# digibuttons.net
KiCad netlist of a schematic drawn in EAGLE
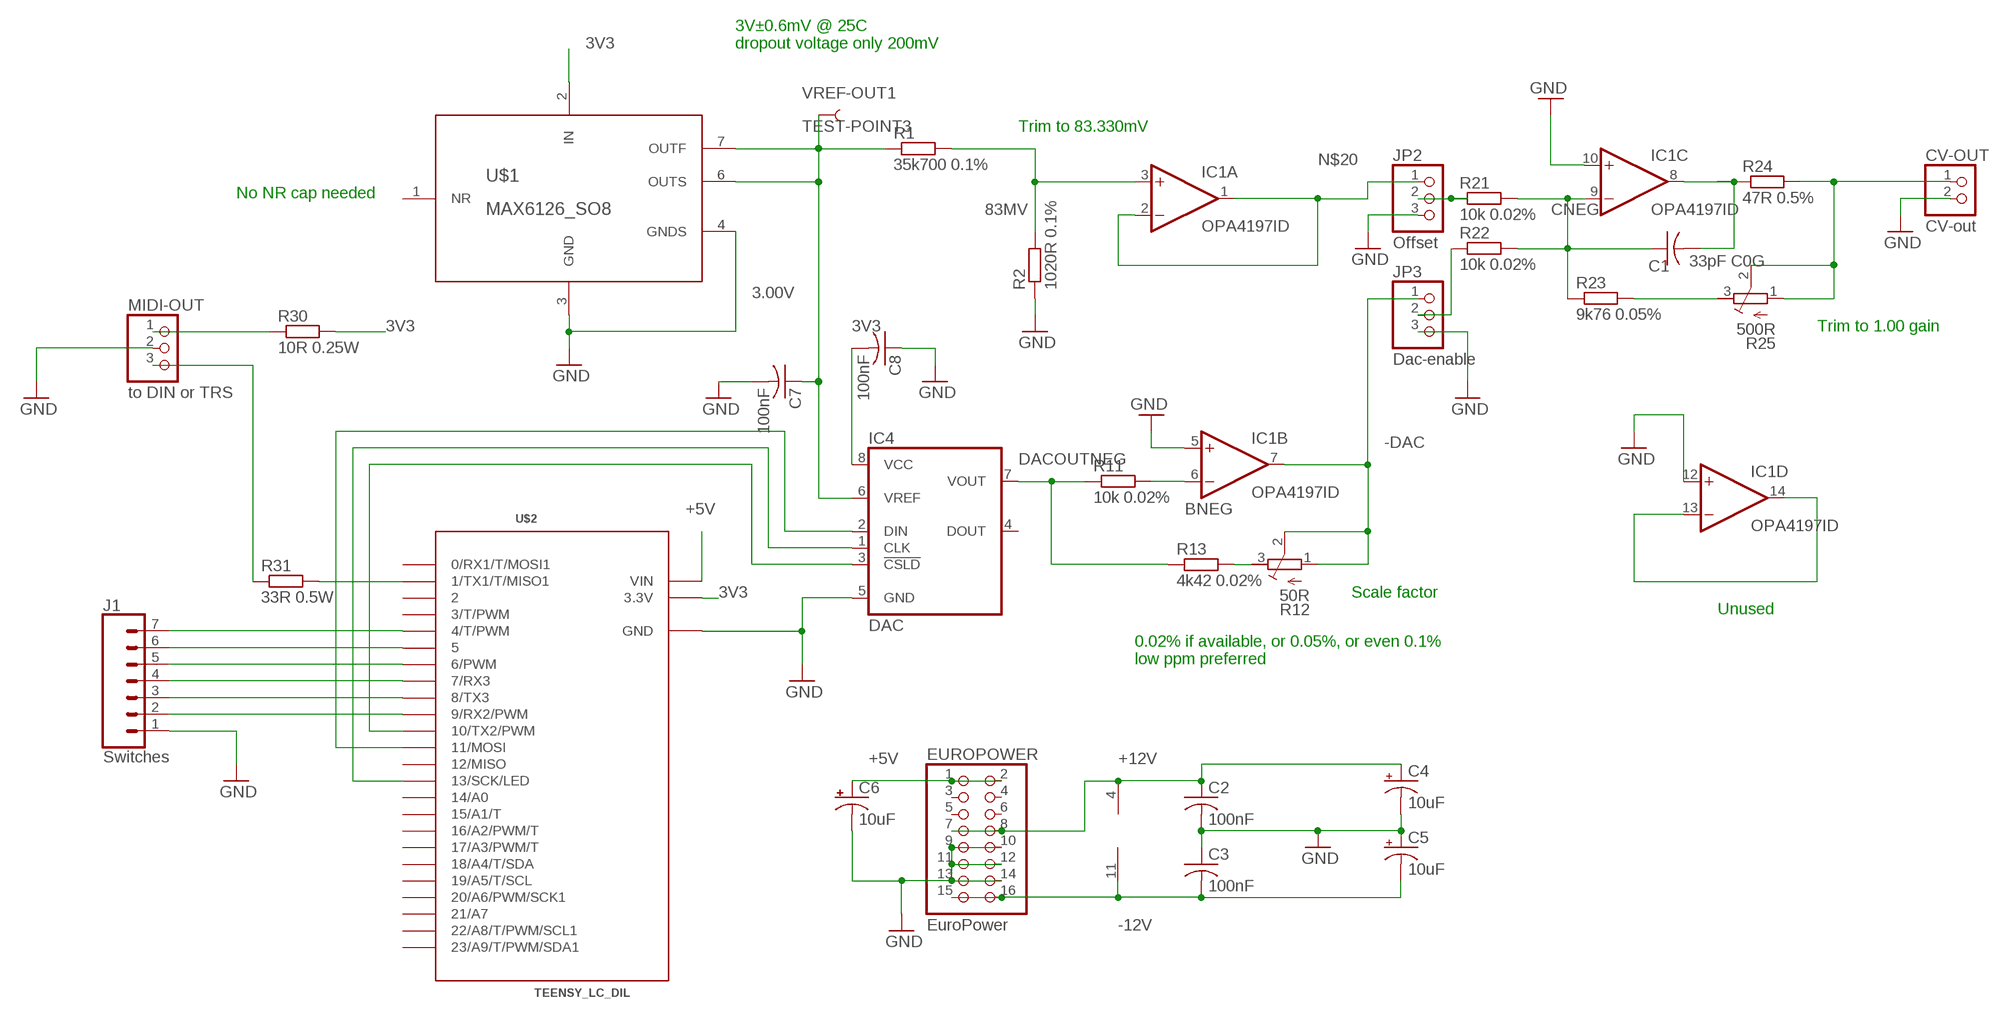
[diagram p0: schematic, sheet 1]

(export (version "E")
  (design (tool "Eeschema 10.0.6"))
  (components
    (comp (ref "C1")
      (value "33pF C0G")
      (footprint "eagle-import:C0805")
      (libsource (lib "eagle-import") (part "C-USC0805"))
    )
    (comp (ref "C2")
      (value "100nF")
      (footprint "eagle-import:C1206")
      (libsource (lib "eagle-import") (part "C-USC1206"))
    )
    (comp (ref "C3")
      (value "100nF")
      (footprint "eagle-import:C1206")
      (libsource (lib "eagle-import") (part "C-USC1206"))
    )
    (comp (ref "C4")
      (value "10uF")
      (footprint "eagle-import:CPOL-RADIAL-2.5MM-5MM")
      (libsource (lib "eagle-import") (part "10UF-POLAR-RADIAL-2.5MM-25V-20%"))
    )
    (comp (ref "C5")
      (value "10uF")
      (footprint "eagle-import:CPOL-RADIAL-2.5MM-5MM")
      (libsource (lib "eagle-import") (part "10UF-POLAR-RADIAL-2.5MM-25V-20%"))
    )
    (comp (ref "C6")
      (value "10uF")
      (footprint "eagle-import:CPOL-RADIAL-2.5MM-5MM")
      (libsource (lib "eagle-import") (part "10UF-POLAR-RADIAL-2.5MM-25V-20%"))
    )
    (comp (ref "C7")
      (value "100nF")
      (footprint "eagle-import:C1206")
      (libsource (lib "eagle-import") (part "C-USC1206"))
    )
    (comp (ref "C8")
      (value "100nF")
      (footprint "eagle-import:C1206")
      (libsource (lib "eagle-import") (part "C-USC1206"))
    )
    (comp (ref "CV-OUT")
      (value "CV-out")
      (footprint "eagle-import:1X02")
      (libsource (lib "eagle-import") (part "PINHD-1X2"))
    )
    (comp (ref "EUROPOWER")
      (value "EuroPower")
      (footprint "eagle-import:2X08")
      (libsource (lib "eagle-import") (part "PINHD-2X8"))
    )
    (comp (ref "IC1")
      (value "OPA4197ID")
      (footprint "eagle-import:SO14")
      (libsource (lib "eagle-import") (part "OPA4743UA"))
    )
    (comp (ref "IC4")
      (value "DAC")
      (footprint "eagle-import:SOIC8_208MIL")
      (libsource (lib "eagle-import") (part "LTC1658CS8SOIC8"))
    )
    (comp (ref "J1")
      (value "Switches")
      (footprint "eagle-import:1X07_LOCK")
      (libsource (lib "eagle-import") (part "CONN_07LOCK"))
    )
    (comp (ref "JP2")
      (value "Offset")
      (footprint "eagle-import:1X03")
      (libsource (lib "eagle-import") (part "PINHD-1X3"))
    )
    (comp (ref "JP3")
      (value "Dac-enable")
      (footprint "eagle-import:1X03")
      (libsource (lib "eagle-import") (part "PINHD-1X3"))
    )
    (comp (ref "MIDI-OUT")
      (value "to DIN or TRS")
      (footprint "eagle-import:1X03")
      (libsource (lib "eagle-import") (part "PINHD-1X3"))
    )
    (comp (ref "R1")
      (value "35k700 0.1%")
      (footprint "eagle-import:R0805")
      (libsource (lib "eagle-import") (part "R-EU_R0805"))
    )
    (comp (ref "R2")
      (value "1020R 0.1%")
      (footprint "eagle-import:R0805")
      (libsource (lib "eagle-import") (part "R-EU_R0805"))
    )
    (comp (ref "R11")
      (value "10k 0.02%")
      (footprint "eagle-import:R0805")
      (libsource (lib "eagle-import") (part "R-EU_R0805"))
    )
    (comp (ref "R12")
      (value "50R")
      (footprint "eagle-import:RTRIM3296W")
      (libsource (lib "eagle-import") (part "R-TRIMM3296W"))
    )
    (comp (ref "R13")
      (value "4k42 0.02%")
      (footprint "eagle-import:R0805")
      (libsource (lib "eagle-import") (part "R-EU_R0805"))
    )
    (comp (ref "R21")
      (value "10k 0.02%")
      (footprint "eagle-import:R0805")
      (libsource (lib "eagle-import") (part "R-EU_R0805"))
    )
    (comp (ref "R22")
      (value "10k 0.02%")
      (footprint "eagle-import:R0805")
      (libsource (lib "eagle-import") (part "R-EU_R0805"))
    )
    (comp (ref "R23")
      (value "9k76 0.05%")
      (footprint "eagle-import:R0805")
      (libsource (lib "eagle-import") (part "R-EU_R0805"))
    )
    (comp (ref "R24")
      (value "47R 0.5%")
      (footprint "eagle-import:R0805")
      (libsource (lib "eagle-import") (part "R-EU_R0805"))
    )
    (comp (ref "R25")
      (value "500R")
      (footprint "eagle-import:RTRIM3296W")
      (libsource (lib "eagle-import") (part "R-TRIMM3296W"))
    )
    (comp (ref "R30")
      (value "10R 0.25W")
      (footprint "eagle-import:10MM_RESISTOR")
      (libsource (lib "eagle-import") (part "RESISTOR10MM_RESISTOR"))
    )
    (comp (ref "R31")
      (value "33R 0.5W")
      (footprint "eagle-import:10MM_RESISTOR")
      (libsource (lib "eagle-import") (part "RESISTOR10MM_RESISTOR"))
    )
    (comp (ref "U$1")
      (value "MAX6126_SO8")
      (footprint "eagle-import:SO08")
      (libsource (lib "eagle-import") (part "MAX6126_SO8"))
    )
    (comp (ref "U$2")
      (value "TEENSY_LC_DIL")
      (footprint "eagle-import:TEENSY_3.0-3.2&LC_DIL")
      (libsource (lib "eagle-import") (part "TEENSY_LC_DIL"))
    )
    (comp (ref "VREF-OUT1")
      (value "TEST-POINT3")
      (footprint "eagle-import:PAD.03X.03")
      (libsource (lib "eagle-import") (part "TEST-POINT3"))
    )
  )
  (nets
    (net (code "1") (name "/+5V") (class "Default")
      (node (ref "C6") (pin "1") (pinfunction "+_1") (pintype "passive"))
      (node (ref "EUROPOWER") (pin "1") (pinfunction "1_1") (pintype "passive"))
      (node (ref "EUROPOWER") (pin "2") (pinfunction "2_2") (pintype "passive"))
      (node (ref "U$2") (pin "VIN") (pinfunction "VIN_VIN") (pintype "power_in"))
    )
    (net (code "2") (name "/+12V") (class "Default")
      (node (ref "C2") (pin "1") (pinfunction "1_1") (pintype "passive"))
      (node (ref "C4") (pin "1") (pinfunction "+_1") (pintype "passive"))
      (node (ref "EUROPOWER") (pin "7") (pinfunction "7_7") (pintype "passive"))
      (node (ref "EUROPOWER") (pin "8") (pinfunction "8_8") (pintype "passive"))
      (node (ref "IC1") (pin "4") (pinfunction "V+_4") (pintype "power_in"))
    )
    (net (code "3") (name "/-12V") (class "Default")
      (node (ref "C3") (pin "2") (pinfunction "2_2") (pintype "passive"))
      (node (ref "C5") (pin "2") (pinfunction "-_2") (pintype "passive"))
      (node (ref "EUROPOWER") (pin "15") (pinfunction "15_15") (pintype "passive"))
      (node (ref "EUROPOWER") (pin "16") (pinfunction "16_16") (pintype "passive"))
      (node (ref "IC1") (pin "11") (pinfunction "V-_11") (pintype "power_in"))
    )
    (net (code "4") (name "/-DAC") (class "Default")
      (node (ref "IC1") (pin "7") (pinfunction "OUT_7") (pintype "output"))
      (node (ref "JP3") (pin "1") (pinfunction "1_1") (pintype "passive"))
      (node (ref "R12") (pin "1") (pinfunction "E_1") (pintype "passive"))
      (node (ref "R12") (pin "2") (pinfunction "S_2") (pintype "passive"))
    )
    (net (code "5") (name "/3.00V") (class "Default")
      (node (ref "C7") (pin "1") (pinfunction "1_1") (pintype "passive"))
      (node (ref "IC4") (pin "6") (pinfunction "VREF_6") (pintype "input"))
      (node (ref "R1") (pin "1") (pinfunction "1_1") (pintype "passive"))
      (node (ref "U$1") (pin "6") (pinfunction "OUTS_6") (pintype "bidirectional"))
      (node (ref "U$1") (pin "7") (pinfunction "OUTF_7") (pintype "bidirectional"))
      (node (ref "VREF-OUT1") (pin "P$1") (pinfunction "1_P$1") (pintype "bidirectional"))
    )
    (net (code "6") (name "/3V3") (class "Default")
      (node (ref "C8") (pin "2") (pinfunction "2_2") (pintype "passive"))
      (node (ref "IC4") (pin "8") (pinfunction "VCC_8") (pintype "power_in"))
      (node (ref "R30") (pin "2") (pinfunction "2_2") (pintype "passive"))
      (node (ref "U$1") (pin "2") (pinfunction "IN_2") (pintype "bidirectional"))
      (node (ref "U$2") (pin "3.3V") (pinfunction "3.3V_3.3V") (pintype "power_in"))
    )
    (net (code "7") (name "/83MV") (class "Default")
      (node (ref "IC1") (pin "3") (pinfunction "+IN_3") (pintype "input"))
      (node (ref "R1") (pin "2") (pinfunction "2_2") (pintype "passive"))
      (node (ref "R2") (pin "2") (pinfunction "2_2") (pintype "passive"))
    )
    (net (code "8") (name "/BNEG") (class "Default")
      (node (ref "IC1") (pin "6") (pinfunction "-IN_6") (pintype "input"))
      (node (ref "R11") (pin "2") (pinfunction "2_2") (pintype "passive"))
    )
    (net (code "9") (name "/CNEG") (class "Default")
      (node (ref "C1") (pin "1") (pinfunction "1_1") (pintype "passive"))
      (node (ref "IC1") (pin "9") (pinfunction "-IN_9") (pintype "input"))
      (node (ref "R21") (pin "2") (pinfunction "2_2") (pintype "passive"))
      (node (ref "R22") (pin "2") (pinfunction "2_2") (pintype "passive"))
      (node (ref "R23") (pin "1") (pinfunction "1_1") (pintype "passive"))
    )
    (net (code "10") (name "/DACOUTNEG") (class "Default")
      (node (ref "IC4") (pin "7") (pinfunction "VOUT_7") (pintype "output"))
      (node (ref "R11") (pin "1") (pinfunction "1_1") (pintype "passive"))
      (node (ref "R13") (pin "1") (pinfunction "1_1") (pintype "passive"))
    )
    (net (code "11") (name "/N$20") (class "Default")
      (node (ref "IC1") (pin "1") (pinfunction "OUT_1") (pintype "output"))
      (node (ref "IC1") (pin "2") (pinfunction "-IN_2") (pintype "input"))
      (node (ref "JP2") (pin "1") (pinfunction "1_1") (pintype "passive"))
    )
    (net (code "12") (name "GND") (class "Default")
      (node (ref "C2") (pin "2") (pinfunction "2_2") (pintype "passive"))
      (node (ref "C3") (pin "1") (pinfunction "1_1") (pintype "passive"))
      (node (ref "C4") (pin "2") (pinfunction "-_2") (pintype "passive"))
      (node (ref "C5") (pin "1") (pinfunction "+_1") (pintype "passive"))
      (node (ref "C6") (pin "2") (pinfunction "-_2") (pintype "passive"))
      (node (ref "C7") (pin "2") (pinfunction "2_2") (pintype "passive"))
      (node (ref "C8") (pin "1") (pinfunction "1_1") (pintype "passive"))
      (node (ref "CV-OUT") (pin "2") (pinfunction "2_2") (pintype "passive"))
      (node (ref "EUROPOWER") (pin "10") (pinfunction "10_10") (pintype "passive"))
      (node (ref "EUROPOWER") (pin "11") (pinfunction "11_11") (pintype "passive"))
      (node (ref "EUROPOWER") (pin "12") (pinfunction "12_12") (pintype "passive"))
      (node (ref "EUROPOWER") (pin "13") (pinfunction "13_13") (pintype "passive"))
      (node (ref "EUROPOWER") (pin "14") (pinfunction "14_14") (pintype "passive"))
      (node (ref "EUROPOWER") (pin "9") (pinfunction "9_9") (pintype "passive"))
      (node (ref "IC1") (pin "10") (pinfunction "+IN_10") (pintype "input"))
      (node (ref "IC1") (pin "12") (pinfunction "+IN_12") (pintype "input"))
      (node (ref "IC1") (pin "5") (pinfunction "+IN_5") (pintype "input"))
      (node (ref "IC4") (pin "5") (pinfunction "GND_5") (pintype "power_in"))
      (node (ref "J1") (pin "1") (pinfunction "1_1") (pintype "passive"))
      (node (ref "JP2") (pin "3") (pinfunction "3_3") (pintype "passive"))
      (node (ref "JP3") (pin "3") (pinfunction "3_3") (pintype "passive"))
      (node (ref "MIDI-OUT") (pin "2") (pinfunction "2_2") (pintype "passive"))
      (node (ref "R2") (pin "1") (pinfunction "1_1") (pintype "passive"))
      (node (ref "U$1") (pin "3") (pinfunction "GND_3") (pintype "bidirectional"))
      (node (ref "U$1") (pin "4") (pinfunction "GNDS_4") (pintype "bidirectional"))
      (node (ref "U$2") (pin "AGND") (pinfunction "GND_AGND") (pintype "power_in"))
      (node (ref "U$2") (pin "GND") (pinfunction "GND_GND") (pintype "power_in"))
    )
    (net (code "13") (name "Net-(IC1C-OUT)") (class "Default")
      (node (ref "C1") (pin "2") (pinfunction "2_2") (pintype "passive"))
      (node (ref "IC1") (pin "8") (pinfunction "OUT_8") (pintype "output"))
      (node (ref "R24") (pin "1") (pinfunction "1_1") (pintype "passive"))
    )
    (net (code "14") (name "Net-(IC1D--IN)") (class "Default")
      (node (ref "IC1") (pin "13") (pinfunction "-IN_13") (pintype "input"))
      (node (ref "IC1") (pin "14") (pinfunction "OUT_14") (pintype "output"))
    )
    (net (code "15") (name "Net-(IC4-CLK)") (class "Default")
      (node (ref "IC4") (pin "1") (pinfunction "CLK_1") (pintype "input"))
      (node (ref "U$2") (pin "13") (pinfunction "13/SCK/LED_13") (pintype "bidirectional"))
    )
    (net (code "16") (name "Net-(IC4-DIN)") (class "Default")
      (node (ref "IC4") (pin "2") (pinfunction "DIN_2") (pintype "input"))
      (node (ref "U$2") (pin "11") (pinfunction "11/MOSI_11") (pintype "bidirectional"))
    )
    (net (code "17") (name "Net-(IC4-~{CSLD})") (class "Default")
      (node (ref "IC4") (pin "3") (pinfunction "~{CSLD}_3") (pintype "input"))
      (node (ref "U$2") (pin "10") (pinfunction "10/TX2/PWM_10") (pintype "bidirectional"))
    )
    (net (code "18") (name "Net-(J1-Pad6)") (class "Default")
      (node (ref "J1") (pin "6") (pinfunction "6_6") (pintype "passive"))
      (node (ref "U$2") (pin "5") (pinfunction "5_5") (pintype "bidirectional"))
    )
    (net (code "19") (name "Net-(JP2-Pad2)") (class "Default")
      (node (ref "JP2") (pin "2") (pinfunction "2_2") (pintype "passive"))
      (node (ref "R21") (pin "1") (pinfunction "1_1") (pintype "passive"))
    )
    (net (code "20") (name "Net-(JP3-Pad2)") (class "Default")
      (node (ref "JP3") (pin "2") (pinfunction "2_2") (pintype "passive"))
      (node (ref "R22") (pin "1") (pinfunction "1_1") (pintype "passive"))
    )
    (net (code "21") (name "Net-(MIDI-OUT-Pad1)") (class "Default")
      (node (ref "MIDI-OUT") (pin "1") (pinfunction "1_1") (pintype "passive"))
      (node (ref "R30") (pin "1") (pinfunction "1_1") (pintype "passive"))
    )
    (net (code "22") (name "Net-(MIDI-OUT-Pad3)") (class "Default")
      (node (ref "MIDI-OUT") (pin "3") (pinfunction "3_3") (pintype "passive"))
      (node (ref "R31") (pin "1") (pinfunction "1_1") (pintype "passive"))
    )
    (net (code "23") (name "Net-(R12-A)") (class "Default")
      (node (ref "R12") (pin "3") (pinfunction "A_3") (pintype "passive"))
      (node (ref "R13") (pin "2") (pinfunction "2_2") (pintype "passive"))
    )
    (net (code "24") (name "Net-(R25-A)") (class "Default")
      (node (ref "R23") (pin "2") (pinfunction "2_2") (pintype "passive"))
      (node (ref "R25") (pin "3") (pinfunction "A_3") (pintype "passive"))
    )
    (net (code "25") (name "Net-(R25-E)") (class "Default")
      (node (ref "CV-OUT") (pin "1") (pinfunction "1_1") (pintype "passive"))
      (node (ref "R24") (pin "2") (pinfunction "2_2") (pintype "passive"))
      (node (ref "R25") (pin "1") (pinfunction "E_1") (pintype "passive"))
      (node (ref "R25") (pin "2") (pinfunction "S_2") (pintype "passive"))
    )
    (net (code "26") (name "Net-(U$2-1{slash}TX1{slash}T{slash}MISO1)") (class "Default")
      (node (ref "R31") (pin "2") (pinfunction "2_2") (pintype "passive"))
      (node (ref "U$2") (pin "1") (pinfunction "1/TX1/T/MISO1_1") (pintype "bidirectional"))
    )
    (net (code "27") (name "Net-(U$2-4{slash}T{slash}PWM)") (class "Default")
      (node (ref "J1") (pin "7") (pinfunction "7_7") (pintype "passive"))
      (node (ref "U$2") (pin "4") (pinfunction "4/T/PWM_4") (pintype "bidirectional"))
    )
    (net (code "28") (name "Net-(U$2-6{slash}PWM)") (class "Default")
      (node (ref "J1") (pin "5") (pinfunction "5_5") (pintype "passive"))
      (node (ref "U$2") (pin "6") (pinfunction "6/PWM_6") (pintype "bidirectional"))
    )
    (net (code "29") (name "Net-(U$2-7{slash}RX3)") (class "Default")
      (node (ref "J1") (pin "4") (pinfunction "4_4") (pintype "passive"))
      (node (ref "U$2") (pin "7") (pinfunction "7/RX3_7") (pintype "bidirectional"))
    )
    (net (code "30") (name "Net-(U$2-8{slash}TX3)") (class "Default")
      (node (ref "J1") (pin "3") (pinfunction "3_3") (pintype "passive"))
      (node (ref "U$2") (pin "8") (pinfunction "8/TX3_8") (pintype "bidirectional"))
    )
    (net (code "31") (name "Net-(U$2-9{slash}RX2{slash}PWM)") (class "Default")
      (node (ref "J1") (pin "2") (pinfunction "2_2") (pintype "passive"))
      (node (ref "U$2") (pin "9") (pinfunction "9/RX2/PWM_9") (pintype "bidirectional"))
    )
    (net (code "32") (name "unconnected-(EUROPOWER-Pad3)") (class "Default")
      (node (ref "EUROPOWER") (pin "3") (pinfunction "3_3") (pintype "passive"))
    )
    (net (code "33") (name "unconnected-(EUROPOWER-Pad4)") (class "Default")
      (node (ref "EUROPOWER") (pin "4") (pinfunction "4_4") (pintype "passive"))
    )
    (net (code "34") (name "unconnected-(EUROPOWER-Pad5)") (class "Default")
      (node (ref "EUROPOWER") (pin "5") (pinfunction "5_5") (pintype "passive"))
    )
    (net (code "35") (name "unconnected-(EUROPOWER-Pad6)") (class "Default")
      (node (ref "EUROPOWER") (pin "6") (pinfunction "6_6") (pintype "passive"))
    )
    (net (code "36") (name "unconnected-(IC4-DOUT-Pad4)") (class "Default")
      (node (ref "IC4") (pin "4") (pinfunction "DOUT_4") (pintype "output"))
    )
    (net (code "37") (name "unconnected-(U$1-NR-Pad1)") (class "Default")
      (node (ref "U$1") (pin "1") (pinfunction "NR_1") (pintype "bidirectional"))
    )
    (net (code "38") (name "unconnected-(U$2-0{slash}RX1{slash}T{slash}MOSI1-Pad0)") (class "Default")
      (node (ref "U$2") (pin "0") (pinfunction "0/RX1/T/MOSI1_0") (pintype "bidirectional"))
    )
    (net (code "39") (name "unconnected-(U$2-3{slash}T{slash}PWM-Pad3)") (class "Default")
      (node (ref "U$2") (pin "3") (pinfunction "3/T/PWM_3") (pintype "bidirectional"))
    )
    (net (code "40") (name "unconnected-(U$2-12{slash}MISO-Pad12)") (class "Default")
      (node (ref "U$2") (pin "12") (pinfunction "12/MISO_12") (pintype "bidirectional"))
    )
    (net (code "41") (name "unconnected-(U$2-15{slash}A1{slash}T-Pad15{slash}A1)") (class "Default")
      (node (ref "U$2") (pin "15/A1") (pinfunction "15/A1/T_15/A1") (pintype "bidirectional"))
    )
    (net (code "42") (name "unconnected-(U$2-16{slash}A2{slash}PWM{slash}T-Pad16{slash}A2)") (class "Default")
      (node (ref "U$2") (pin "16/A2") (pinfunction "16/A2/PWM/T_16/A2") (pintype "bidirectional"))
    )
    (net (code "43") (name "unconnected-(U$2-17{slash}A3{slash}PWM{slash}T-Pad17{slash}A3)") (class "Default")
      (node (ref "U$2") (pin "17/A3") (pinfunction "17/A3/PWM/T_17/A3") (pintype "bidirectional"))
    )
    (net (code "44") (name "unconnected-(U$2-18{slash}A4{slash}T{slash}SDA-Pad18{slash}A4)") (class "Default")
      (node (ref "U$2") (pin "18/A4") (pinfunction "18/A4/T/SDA_18/A4") (pintype "bidirectional"))
    )
    (net (code "45") (name "unconnected-(U$2-19{slash}A5{slash}T{slash}SCL-Pad19{slash}A5)") (class "Default")
      (node (ref "U$2") (pin "19/A5") (pinfunction "19/A5/T/SCL_19/A5") (pintype "bidirectional"))
    )
    (net (code "46") (name "unconnected-(U$2-20{slash}A6{slash}PWM{slash}SCK1-Pad20{slash}A6)") (class "Default")
      (node (ref "U$2") (pin "20/A6") (pinfunction "20/A6/PWM/SCK1_20/A6") (pintype "bidirectional"))
    )
    (net (code "47") (name "unconnected-(U$2-22{slash}A8{slash}T{slash}PWM{slash}SCL1-Pad22{slash}A8)") (class "Default")
      (node (ref "U$2") (pin "22/A8") (pinfunction "22/A8/T/PWM/SCL1_22/A8") (pintype "bidirectional"))
    )
    (net (code "48") (name "unconnected-(U$2-23{slash}A9{slash}T{slash}PWM{slash}SDA1-Pad23{slash}A9)") (class "Default")
      (node (ref "U$2") (pin "23/A9") (pinfunction "23/A9/T/PWM/SDA1_23/A9") (pintype "bidirectional"))
    )
    (net (code "49") (name "unconnected-(U$2-Pad2)") (class "Default")
      (node (ref "U$2") (pin "2") (pinfunction "2_2") (pintype "bidirectional"))
    )
    (net (code "50") (name "unconnected-(U$2-Pad14{slash}A0)") (class "Default")
      (node (ref "U$2") (pin "14/A0") (pinfunction "14/A0_14/A0") (pintype "bidirectional"))
    )
    (net (code "51") (name "unconnected-(U$2-Pad21{slash}A7)") (class "Default")
      (node (ref "U$2") (pin "21/A7") (pinfunction "21/A7_21/A7") (pintype "bidirectional"))
    )
  )
)
